# Sensors.net
KiCad netlist of a schematic drawn in Altium Designer
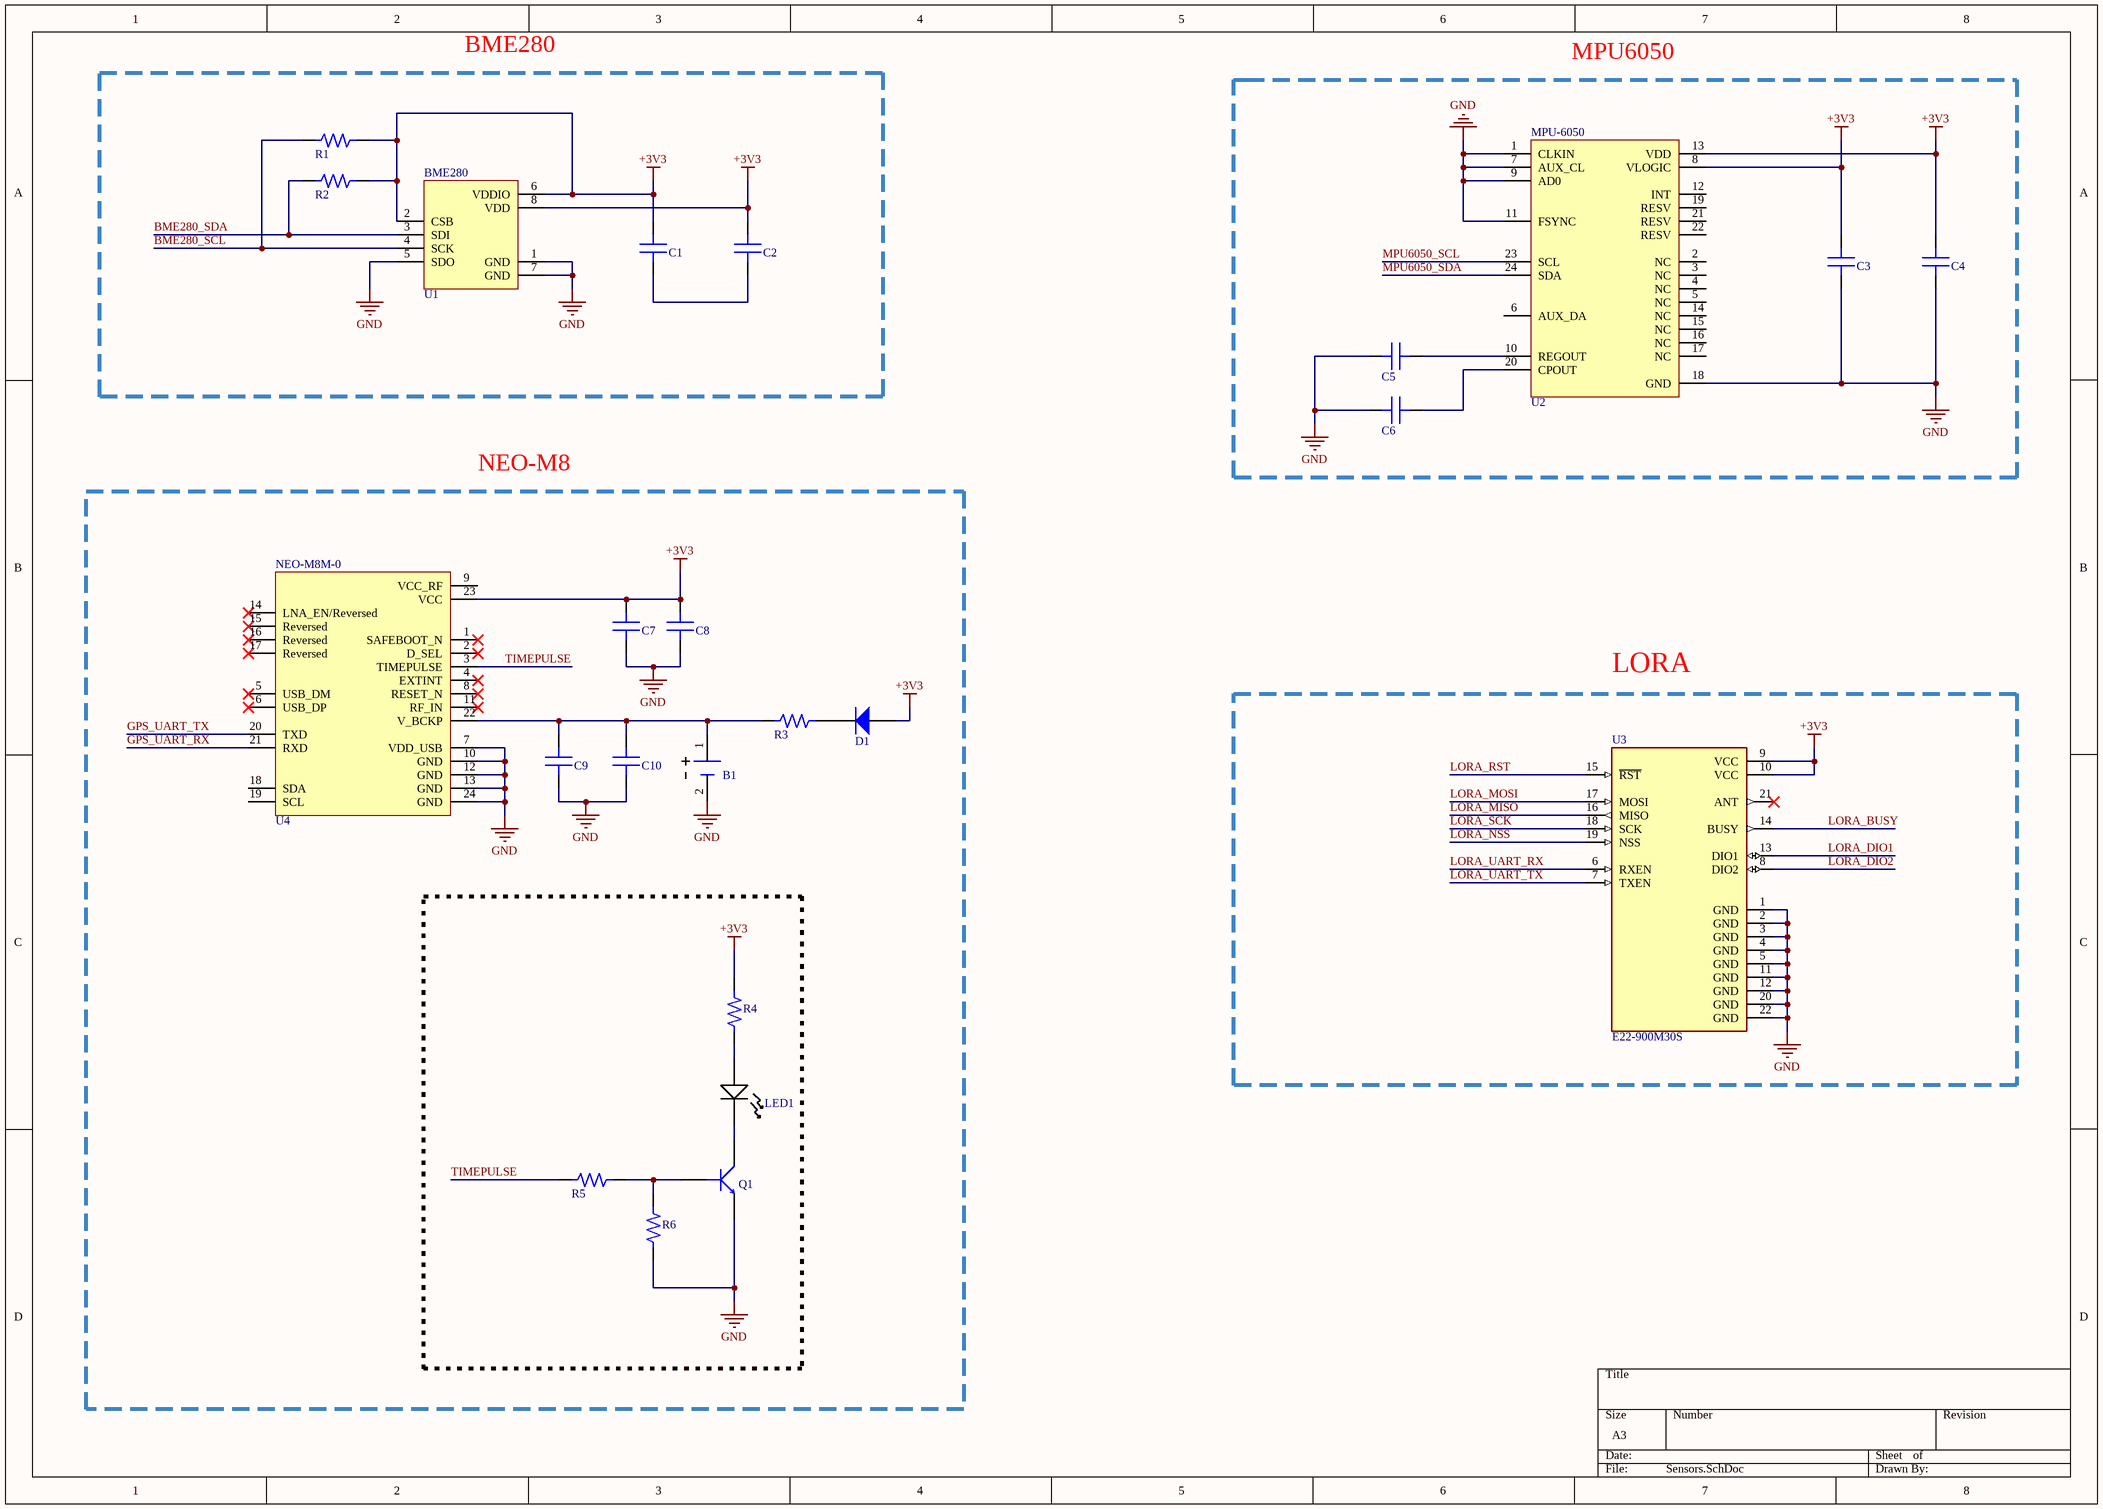
[diagram p0: Sensors.SchDoc]

(export (version "E")
  (design (tool "Eeschema 10.0.6"))
  (components
    (comp (ref "B1")
      (value "MS920SE-FL27E")
      (footprint "MS920SE_Battery")
      (description "Lithium Battery Coin 3V 11mAh Rechargeable Tray")
      (fields (field (name "MANUFACTURER") "Epson") (field (name "VOLTAGE") "3V"))
      (libsource (lib "ROKET_LIBRARY") (part "BATTERY"))
    )
    (comp (ref "C1")
      (value "CAP CER 100nF 0805")
      (footprint "CAP_0805")
      (libsource (lib "ROKET_LIBRARY") (part "CAP CER 100nF 0805"))
    )
    (comp (ref "C2")
      (value "CAP CER 100nF 0805")
      (footprint "CAP_0805")
      (libsource (lib "ROKET_LIBRARY") (part "CAP CER 100nF 0805"))
    )
    (comp (ref "C3")
      (value "CAP CER 10nF 0805")
      (footprint "CAP_0805")
      (libsource (lib "ROKET_LIBRARY") (part "CAP CER 10nF 0805"))
    )
    (comp (ref "C4")
      (value "CAP CER 0.1uF 0805")
      (footprint "CAP_0805")
      (libsource (lib "ROKET_LIBRARY") (part "CAP CER 0.1uF 0805"))
    )
    (comp (ref "C5")
      (value "CAP CER 0.1uF 0805")
      (footprint "CAP_0805")
      (libsource (lib "ROKET_LIBRARY") (part "CAP CER 0.1uF 0805"))
    )
    (comp (ref "C6")
      (value "CAP CER 2.2nF 0805")
      (footprint "CAP_0805")
      (libsource (lib "ROKET_LIBRARY") (part "CAP CER 2.2nF 0805"))
    )
    (comp (ref "C7")
      (value "CAP CER 10uF 0805")
      (footprint "CAP_0805")
      (libsource (lib "ROKET_LIBRARY") (part "CAP CER 10uF 0805"))
    )
    (comp (ref "C8")
      (value "CAP CER 100nF 0805")
      (footprint "CAP_0805")
      (libsource (lib "ROKET_LIBRARY") (part "CAP CER 100nF 0805"))
    )
    (comp (ref "C9")
      (value "CAP CER 4.7uF 0805")
      (footprint "CAP_0805")
      (libsource (lib "ROKET_LIBRARY") (part "CAP CER 4.7uF 0805"))
    )
    (comp (ref "C10")
      (value "CAP CER 100nF 0805")
      (footprint "CAP_0805")
      (libsource (lib "ROKET_LIBRARY") (part "CAP CER 100nF 0805"))
    )
    (comp (ref "D1")
      (value "DIODE GEN PURP 75V 150MA SOD323F")
      (footprint "SOD323F")
      (description "VR=75V IF=150mA Trr=4ns P=200mW")
      (fields
        (field (name "MANUFACTURER") "ON Semiconductor / Fairchild")
        (field (name "MANUFACTURER PART NUMBER") "1N4148WS")
      )
      (libsource (lib "ROKET_LIBRARY") (part "DIODE"))
    )
    (comp (ref "LED1")
      (value "CMD17-21VRD/TR8")
      (footprint "LED RED_0805")
      (description "LED Uni-Color Red 640nm 2-Pin SMT T/R")
      (fields (field (name "MANUFACTURER") "VCC CHML"))
      (libsource (lib "ROKET_LIBRARY") (part "LED RED"))
    )
    (comp (ref "Q1")
      (value "MMBT3904-7-F")
      (footprint "SOT_23F")
      (description "NPN Ic=200mA Vceo=40V hfe=100~300 fT=310MHz P=300mW SOT-23")
      (fields (field (name "MANUFACTURER") "Diodes Zetex"))
      (libsource (lib "ROKET_LIBRARY") (part "BJT_NPN"))
    )
    (comp (ref "R1")
      (value "RES 4.7K OHM 0805")
      (footprint "RES_0805")
      (libsource (lib "ROKET_LIBRARY") (part "RES 4.7K OHM 0805"))
    )
    (comp (ref "R2")
      (value "RES 4.7K OHM 0805")
      (footprint "RES_0805")
      (libsource (lib "ROKET_LIBRARY") (part "RES 4.7K OHM 0805"))
    )
    (comp (ref "R3")
      (value "RES 1K OHM 0805")
      (footprint "RES_0805")
      (libsource (lib "ROKET_LIBRARY") (part "RES 1K OHM 0805"))
    )
    (comp (ref "R4")
      (value "RES 1K OHM 0805")
      (footprint "RES_0805")
      (libsource (lib "ROKET_LIBRARY") (part "RES 1K OHM 0805"))
    )
    (comp (ref "R5")
      (value "RES 10K OHM 0805")
      (footprint "RES_0805")
      (libsource (lib "ROKET_LIBRARY") (part "RES 10K OHM 0805"))
    )
    (comp (ref "R6")
      (value "RES 10K OHM 0805")
      (footprint "RES_0805")
      (libsource (lib "ROKET_LIBRARY") (part "RES 10K OHM 0805"))
    )
    (comp (ref "U1")
      (value "BME280")
      (footprint "BME280")
      (description "Pressure, Temperature and Humidity Sensor Digital Output 1.8V 8-Pin LGA T/R")
      (fields (field (name "MANUFACTURER") "Bosch Tools"))
      (libsource (lib "ROKET_LIBRARY") (part "BME280"))
    )
    (comp (ref "U2")
      (value "MPU-6050")
      (footprint "QFN-24-MPU6050")
      (description "IMU ACCEL/GYRO 3-AXIS I2C 24QFN")
      (fields (field (name "MANUFACTURER") "TDK InvenSense"))
      (libsource (lib "ROKET_LIBRARY") (part "MPU6050"))
    )
    (comp (ref "U3")
      (value "E22-900M30S")
      (footprint "LORA")
      (description "SX1262 868/915 MHz 1w SPI LoRa Module")
      (fields (field (name "MF") "EBYTE"))
      (libsource (lib "İSRA_ROKET") (part "LORA"))
    )
    (comp (ref "U4")
      (value "NEO-M8M-0")
      (footprint "NEO-M8-GPS")
      (description "Rf Rcvr Gnss/gps 1.575GHZ 24LCC")
      (fields (field (name "MANUFACTURER") "u-blox"))
      (libsource (lib "ROKET_LIBRARY") (part "NEO-M8"))
    )
  )
  (nets
    (net (code "1") (name "+3V3") (class "Default")
      (node (ref "C1") (pin "2") (pinfunction "2_2") (pintype "passive"))
      (node (ref "C2") (pin "2") (pinfunction "2_2") (pintype "passive"))
      (node (ref "C3") (pin "2") (pinfunction "2_2") (pintype "passive"))
      (node (ref "C4") (pin "2") (pinfunction "2_2") (pintype "passive"))
      (node (ref "C7") (pin "2") (pinfunction "2_2") (pintype "passive"))
      (node (ref "C8") (pin "2") (pinfunction "2_2") (pintype "passive"))
      (node (ref "D1") (pin "2") (pinfunction "ANODE_2") (pintype "passive"))
      (node (ref "R1") (pin "2") (pinfunction "2_2") (pintype "passive"))
      (node (ref "R2") (pin "2") (pinfunction "2_2") (pintype "passive"))
      (node (ref "R4") (pin "2") (pinfunction "2_2") (pintype "passive"))
      (node (ref "U1") (pin "2") (pinfunction "CSB_2") (pintype "passive"))
      (node (ref "U1") (pin "6") (pinfunction "VDDIO_6") (pintype "passive"))
      (node (ref "U1") (pin "8") (pinfunction "VDD_8") (pintype "passive"))
      (node (ref "U2") (pin "13") (pinfunction "VDD_13") (pintype "passive"))
      (node (ref "U2") (pin "8") (pinfunction "VLOGIC_8") (pintype "passive"))
      (node (ref "U3") (pin "10") (pinfunction "VCC_10") (pintype "power_in"))
      (node (ref "U3") (pin "9") (pinfunction "VCC_9") (pintype "power_in"))
      (node (ref "U4") (pin "23") (pinfunction "VCC_23") (pintype "passive"))
    )
    (net (code "2") (name "/BME280_SCL") (class "Default")
      (node (ref "R1") (pin "1") (pinfunction "1_1") (pintype "passive"))
      (node (ref "U1") (pin "4") (pinfunction "SCK_4") (pintype "passive"))
    )
    (net (code "3") (name "/BME280_SDA") (class "Default")
      (node (ref "R2") (pin "1") (pinfunction "1_1") (pintype "passive"))
      (node (ref "U1") (pin "3") (pinfunction "SDI_3") (pintype "passive"))
    )
    (net (code "4") (name "/GPS_UART_RX") (class "Default")
      (node (ref "U4") (pin "21") (pinfunction "RXD_21") (pintype "passive"))
    )
    (net (code "5") (name "/GPS_UART_TX") (class "Default")
      (node (ref "U4") (pin "20") (pinfunction "TXD_20") (pintype "passive"))
    )
    (net (code "6") (name "/LORA_BUSY") (class "Default")
      (node (ref "U3") (pin "14") (pinfunction "BUSY_14") (pintype "output"))
    )
    (net (code "7") (name "/LORA_DIO1") (class "Default")
      (node (ref "U3") (pin "13") (pinfunction "DIO1_13") (pintype "bidirectional"))
    )
    (net (code "8") (name "/LORA_DIO2") (class "Default")
      (node (ref "U3") (pin "8") (pinfunction "DIO2_8") (pintype "bidirectional"))
    )
    (net (code "9") (name "/LORA_MISO") (class "Default")
      (node (ref "U3") (pin "16") (pinfunction "MISO_16") (pintype "output"))
    )
    (net (code "10") (name "/LORA_MOSI") (class "Default")
      (node (ref "U3") (pin "17") (pinfunction "MOSI_17") (pintype "input"))
    )
    (net (code "11") (name "/LORA_NSS") (class "Default")
      (node (ref "U3") (pin "19") (pinfunction "NSS_19") (pintype "input"))
    )
    (net (code "12") (name "/LORA_RST") (class "Default")
      (node (ref "U3") (pin "15") (pinfunction "~{RST}_15") (pintype "input"))
    )
    (net (code "13") (name "/LORA_SCK") (class "Default")
      (node (ref "U3") (pin "18") (pinfunction "SCK_18") (pintype "input"))
    )
    (net (code "14") (name "/LORA_UART_RX") (class "Default")
      (node (ref "U3") (pin "6") (pinfunction "RXEN_6") (pintype "input"))
    )
    (net (code "15") (name "/LORA_UART_TX") (class "Default")
      (node (ref "U3") (pin "7") (pinfunction "TXEN_7") (pintype "input"))
    )
    (net (code "16") (name "/MPU6050_SCL") (class "Default")
      (node (ref "U2") (pin "23") (pinfunction "SCL_23") (pintype "passive"))
    )
    (net (code "17") (name "/MPU6050_SDA") (class "Default")
      (node (ref "U2") (pin "24") (pinfunction "SDA_24") (pintype "passive"))
    )
    (net (code "18") (name "/TIMEPULSE") (class "Default")
      (node (ref "R5") (pin "1") (pinfunction "1_1") (pintype "passive"))
      (node (ref "U4") (pin "3") (pinfunction "TIMEPULSE_3") (pintype "passive"))
    )
    (net (code "19") (name "GND") (class "Default")
      (node (ref "B1") (pin "2") (pinfunction "2_2") (pintype "passive"))
      (node (ref "C10") (pin "1") (pinfunction "1_1") (pintype "passive"))
      (node (ref "C3") (pin "1") (pinfunction "1_1") (pintype "passive"))
      (node (ref "C4") (pin "1") (pinfunction "1_1") (pintype "passive"))
      (node (ref "C5") (pin "1") (pinfunction "1_1") (pintype "passive"))
      (node (ref "C6") (pin "1") (pinfunction "1_1") (pintype "passive"))
      (node (ref "C7") (pin "1") (pinfunction "1_1") (pintype "passive"))
      (node (ref "C8") (pin "1") (pinfunction "1_1") (pintype "passive"))
      (node (ref "C9") (pin "1") (pinfunction "1_1") (pintype "passive"))
      (node (ref "Q1") (pin "2") (pinfunction "E_2") (pintype "passive"))
      (node (ref "R6") (pin "1") (pinfunction "1_1") (pintype "passive"))
      (node (ref "U1") (pin "1") (pinfunction "GND_1") (pintype "passive"))
      (node (ref "U1") (pin "5") (pinfunction "SDO_5") (pintype "passive"))
      (node (ref "U1") (pin "7") (pinfunction "GND_7") (pintype "passive"))
      (node (ref "U2") (pin "1") (pinfunction "CLKIN_1") (pintype "passive"))
      (node (ref "U2") (pin "11") (pinfunction "FSYNC_11") (pintype "passive"))
      (node (ref "U2") (pin "18") (pinfunction "GND_18") (pintype "passive"))
      (node (ref "U2") (pin "7") (pinfunction "AUX_CL_7") (pintype "passive"))
      (node (ref "U2") (pin "9") (pinfunction "AD0_9") (pintype "passive"))
      (node (ref "U3") (pin "1") (pinfunction "GND_1") (pintype "power_in"))
      (node (ref "U3") (pin "11") (pinfunction "GND_11") (pintype "power_in"))
      (node (ref "U3") (pin "12") (pinfunction "GND_12") (pintype "power_in"))
      (node (ref "U3") (pin "2") (pinfunction "GND_2") (pintype "power_in"))
      (node (ref "U3") (pin "20") (pinfunction "GND_20") (pintype "power_in"))
      (node (ref "U3") (pin "22") (pinfunction "GND_22") (pintype "power_in"))
      (node (ref "U3") (pin "3") (pinfunction "GND_3") (pintype "power_in"))
      (node (ref "U3") (pin "4") (pinfunction "GND_4") (pintype "power_in"))
      (node (ref "U3") (pin "5") (pinfunction "GND_5") (pintype "power_in"))
      (node (ref "U4") (pin "10") (pinfunction "GND_10") (pintype "passive"))
      (node (ref "U4") (pin "12") (pinfunction "GND_12") (pintype "passive"))
      (node (ref "U4") (pin "13") (pinfunction "GND_13") (pintype "passive"))
      (node (ref "U4") (pin "24") (pinfunction "GND_24") (pintype "passive"))
      (node (ref "U4") (pin "7") (pinfunction "VDD_USB_7") (pintype "passive"))
    )
    (net (code "20") (name "Net-(C1-Pad1)") (class "Default")
      (node (ref "C1") (pin "1") (pinfunction "1_1") (pintype "passive"))
      (node (ref "C2") (pin "1") (pinfunction "1_1") (pintype "passive"))
    )
    (net (code "21") (name "Net-(D1-CATHODE)") (class "Default")
      (node (ref "D1") (pin "1") (pinfunction "CATHODE_1") (pintype "passive"))
      (node (ref "R3") (pin "2") (pinfunction "2_2") (pintype "passive"))
    )
    (net (code "22") (name "Net-(LED1-Pad1)") (class "Default")
      (node (ref "LED1") (pin "1") (pinfunction "1_1") (pintype "passive"))
      (node (ref "R4") (pin "1") (pinfunction "1_1") (pintype "passive"))
    )
    (net (code "23") (name "Net-(Q1-B)") (class "Default")
      (node (ref "Q1") (pin "1") (pinfunction "B_1") (pintype "passive"))
      (node (ref "R5") (pin "2") (pinfunction "2_2") (pintype "passive"))
      (node (ref "R6") (pin "2") (pinfunction "2_2") (pintype "passive"))
    )
    (net (code "24") (name "Net-(Q1-C)") (class "Default")
      (node (ref "LED1") (pin "2") (pinfunction "2_2") (pintype "passive"))
      (node (ref "Q1") (pin "3") (pinfunction "C_3") (pintype "passive"))
    )
    (net (code "25") (name "Net-(U2-CPOUT)") (class "Default")
      (node (ref "C6") (pin "2") (pinfunction "2_2") (pintype "passive"))
      (node (ref "U2") (pin "20") (pinfunction "CPOUT_20") (pintype "passive"))
    )
    (net (code "26") (name "Net-(U2-REGOUT)") (class "Default")
      (node (ref "C5") (pin "2") (pinfunction "2_2") (pintype "passive"))
      (node (ref "U2") (pin "10") (pinfunction "REGOUT_10") (pintype "passive"))
    )
    (net (code "27") (name "Net-(U4-V_BCKP)") (class "Default")
      (node (ref "B1") (pin "1") (pinfunction "1_1") (pintype "passive"))
      (node (ref "C10") (pin "2") (pinfunction "2_2") (pintype "passive"))
      (node (ref "C9") (pin "2") (pinfunction "2_2") (pintype "passive"))
      (node (ref "R3") (pin "1") (pinfunction "1_1") (pintype "passive"))
      (node (ref "U4") (pin "22") (pinfunction "V_BCKP_22") (pintype "passive"))
    )
    (net (code "28") (name "unconnected-(U2-AUX_DA-Pad6)") (class "Default")
      (node (ref "U2") (pin "6") (pinfunction "AUX_DA_6") (pintype "passive"))
    )
    (net (code "29") (name "unconnected-(U2-INT-Pad12)") (class "Default")
      (node (ref "U2") (pin "12") (pinfunction "INT_12") (pintype "passive"))
    )
    (net (code "30") (name "unconnected-(U2-NC-Pad2)") (class "Default")
      (node (ref "U2") (pin "2") (pinfunction "NC_2") (pintype "passive"))
    )
    (net (code "31") (name "unconnected-(U2-NC-Pad3)") (class "Default")
      (node (ref "U2") (pin "3") (pinfunction "NC_3") (pintype "passive"))
    )
    (net (code "32") (name "unconnected-(U2-NC-Pad4)") (class "Default")
      (node (ref "U2") (pin "4") (pinfunction "NC_4") (pintype "passive"))
    )
    (net (code "33") (name "unconnected-(U2-NC-Pad5)") (class "Default")
      (node (ref "U2") (pin "5") (pinfunction "NC_5") (pintype "passive"))
    )
    (net (code "34") (name "unconnected-(U2-NC-Pad14)") (class "Default")
      (node (ref "U2") (pin "14") (pinfunction "NC_14") (pintype "passive"))
    )
    (net (code "35") (name "unconnected-(U2-NC-Pad15)") (class "Default")
      (node (ref "U2") (pin "15") (pinfunction "NC_15") (pintype "passive"))
    )
    (net (code "36") (name "unconnected-(U2-NC-Pad16)") (class "Default")
      (node (ref "U2") (pin "16") (pinfunction "NC_16") (pintype "passive"))
    )
    (net (code "37") (name "unconnected-(U2-NC-Pad17)") (class "Default")
      (node (ref "U2") (pin "17") (pinfunction "NC_17") (pintype "passive"))
    )
    (net (code "38") (name "unconnected-(U2-RESV-Pad19)") (class "Default")
      (node (ref "U2") (pin "19") (pinfunction "RESV_19") (pintype "passive"))
    )
    (net (code "39") (name "unconnected-(U2-RESV-Pad21)") (class "Default")
      (node (ref "U2") (pin "21") (pinfunction "RESV_21") (pintype "passive"))
    )
    (net (code "40") (name "unconnected-(U2-RESV-Pad22)") (class "Default")
      (node (ref "U2") (pin "22") (pinfunction "RESV_22") (pintype "passive"))
    )
    (net (code "41") (name "unconnected-(U3-ANT-Pad21)") (class "Default")
      (node (ref "U3") (pin "21") (pinfunction "ANT_21") (pintype "output+no_connect"))
    )
    (net (code "42") (name "unconnected-(U4-D_SEL-Pad2)") (class "Default")
      (node (ref "U4") (pin "2") (pinfunction "D_SEL_2") (pintype "passive+no_connect"))
    )
    (net (code "43") (name "unconnected-(U4-EXTINT-Pad4)") (class "Default")
      (node (ref "U4") (pin "4") (pinfunction "EXTINT_4") (pintype "passive+no_connect"))
    )
    (net (code "44") (name "unconnected-(U4-LNA_EN{slash}Reversed-Pad14)") (class "Default")
      (node (ref "U4") (pin "14") (pinfunction "LNA_EN/Reversed_14") (pintype "passive+no_connect"))
    )
    (net (code "45") (name "unconnected-(U4-RESET_N-Pad8)") (class "Default")
      (node (ref "U4") (pin "8") (pinfunction "RESET_N_8") (pintype "passive+no_connect"))
    )
    (net (code "46") (name "unconnected-(U4-RF_IN-Pad11)") (class "Default")
      (node (ref "U4") (pin "11") (pinfunction "RF_IN_11") (pintype "passive+no_connect"))
    )
    (net (code "47") (name "unconnected-(U4-Reversed-Pad15)") (class "Default")
      (node (ref "U4") (pin "15") (pinfunction "Reversed_15") (pintype "passive+no_connect"))
    )
    (net (code "48") (name "unconnected-(U4-Reversed-Pad16)") (class "Default")
      (node (ref "U4") (pin "16") (pinfunction "Reversed_16") (pintype "passive+no_connect"))
    )
    (net (code "49") (name "unconnected-(U4-Reversed-Pad17)") (class "Default")
      (node (ref "U4") (pin "17") (pinfunction "Reversed_17") (pintype "passive+no_connect"))
    )
    (net (code "50") (name "unconnected-(U4-SAFEBOOT_N-Pad1)") (class "Default")
      (node (ref "U4") (pin "1") (pinfunction "SAFEBOOT_N_1") (pintype "passive+no_connect"))
    )
    (net (code "51") (name "unconnected-(U4-SCL-Pad19)") (class "Default")
      (node (ref "U4") (pin "19") (pinfunction "SCL_19") (pintype "passive"))
    )
    (net (code "52") (name "unconnected-(U4-SDA-Pad18)") (class "Default")
      (node (ref "U4") (pin "18") (pinfunction "SDA_18") (pintype "passive"))
    )
    (net (code "53") (name "unconnected-(U4-USB_DM-Pad5)") (class "Default")
      (node (ref "U4") (pin "5") (pinfunction "USB_DM_5") (pintype "passive+no_connect"))
    )
    (net (code "54") (name "unconnected-(U4-USB_DP-Pad6)") (class "Default")
      (node (ref "U4") (pin "6") (pinfunction "USB_DP_6") (pintype "passive+no_connect"))
    )
    (net (code "55") (name "unconnected-(U4-VCC_RF-Pad9)") (class "Default")
      (node (ref "U4") (pin "9") (pinfunction "VCC_RF_9") (pintype "passive"))
    )
  )
)
